# 24-SMD-adapter.net
KiCad netlist of a schematic drawn in EAGLE
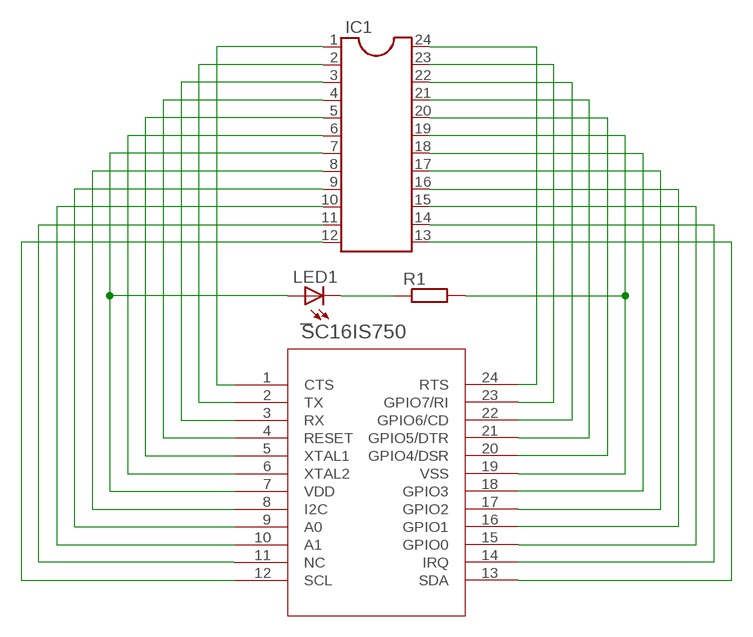
[diagram p0: schematic, sheet 1]

(export (version "E")
  (design (tool "Eeschema 10.0.6"))
  (components
    (comp (ref "IC1")
      (value "DIL24-6")
      (footprint "eagle-import:DIL24-6")
      (libsource (lib "eagle-import") (part "DIL24-6"))
    )
    (comp (ref "LED1")
      (value "LEDSML1206")
      (footprint "eagle-import:SML1206")
      (libsource (lib "eagle-import") (part "LEDSML1206"))
    )
    (comp (ref "R1")
      (value "R-EU_R0402")
      (footprint "eagle-import:R0402")
      (libsource (lib "eagle-import") (part "R-EU_R0402"))
    )
    (comp (ref "_")
      (value "SC16IS750")
      (footprint "eagle-import:SOT361_1_M")
      (libsource (lib "eagle-import") (part "SC16IS750"))
    )
  )
  (nets
    (net (code "1") (name "Net-(LED1-PadC)") (class "Default")
      (node (ref "LED1") (pin "C") (pinfunction "C_C") (pintype "passive"))
      (node (ref "R1") (pin "1") (pinfunction "1_1") (pintype "passive"))
    )
    (net (code "2") (name "Net-(_-A0)") (class "Default")
      (node (ref "IC1") (pin "9") (pinfunction "9_9") (pintype "passive"))
      (node (ref "_") (pin "9") (pinfunction "A0_9") (pintype "passive"))
    )
    (net (code "3") (name "Net-(_-A1)") (class "Default")
      (node (ref "IC1") (pin "10") (pinfunction "10_10") (pintype "passive"))
      (node (ref "_") (pin "10") (pinfunction "A1_10") (pintype "passive"))
    )
    (net (code "4") (name "Net-(_-CTS)") (class "Default")
      (node (ref "IC1") (pin "1") (pinfunction "1_1") (pintype "passive"))
      (node (ref "_") (pin "1") (pinfunction "CTS_1") (pintype "passive"))
    )
    (net (code "5") (name "Net-(_-GPIO0)") (class "Default")
      (node (ref "IC1") (pin "15") (pinfunction "15_15") (pintype "passive"))
      (node (ref "_") (pin "15") (pinfunction "GPIO0_15") (pintype "passive"))
    )
    (net (code "6") (name "Net-(_-GPIO1)") (class "Default")
      (node (ref "IC1") (pin "16") (pinfunction "16_16") (pintype "passive"))
      (node (ref "_") (pin "16") (pinfunction "GPIO1_16") (pintype "passive"))
    )
    (net (code "7") (name "Net-(_-GPIO2)") (class "Default")
      (node (ref "IC1") (pin "17") (pinfunction "17_17") (pintype "passive"))
      (node (ref "_") (pin "17") (pinfunction "GPIO2_17") (pintype "passive"))
    )
    (net (code "8") (name "Net-(_-GPIO3)") (class "Default")
      (node (ref "IC1") (pin "18") (pinfunction "18_18") (pintype "passive"))
      (node (ref "_") (pin "18") (pinfunction "GPIO3_18") (pintype "passive"))
    )
    (net (code "9") (name "Net-(_-GPIO4{slash}DSR)") (class "Default")
      (node (ref "IC1") (pin "20") (pinfunction "20_20") (pintype "passive"))
      (node (ref "_") (pin "20") (pinfunction "GPIO4/DSR_20") (pintype "passive"))
    )
    (net (code "10") (name "Net-(_-GPIO5{slash}DTR)") (class "Default")
      (node (ref "IC1") (pin "21") (pinfunction "21_21") (pintype "passive"))
      (node (ref "_") (pin "21") (pinfunction "GPIO5/DTR_21") (pintype "passive"))
    )
    (net (code "11") (name "Net-(_-GPIO6{slash}CD)") (class "Default")
      (node (ref "IC1") (pin "22") (pinfunction "22_22") (pintype "passive"))
      (node (ref "_") (pin "22") (pinfunction "GPIO6/CD_22") (pintype "passive"))
    )
    (net (code "12") (name "Net-(_-GPIO7{slash}RI)") (class "Default")
      (node (ref "IC1") (pin "23") (pinfunction "23_23") (pintype "passive"))
      (node (ref "_") (pin "23") (pinfunction "GPIO7/RI_23") (pintype "passive"))
    )
    (net (code "13") (name "Net-(_-I2C)") (class "Default")
      (node (ref "IC1") (pin "8") (pinfunction "8_8") (pintype "passive"))
      (node (ref "_") (pin "8") (pinfunction "I2C_8") (pintype "passive"))
    )
    (net (code "14") (name "Net-(_-IRQ)") (class "Default")
      (node (ref "IC1") (pin "14") (pinfunction "14_14") (pintype "passive"))
      (node (ref "_") (pin "14") (pinfunction "IRQ_14") (pintype "passive"))
    )
    (net (code "15") (name "Net-(_-NC)") (class "Default")
      (node (ref "IC1") (pin "11") (pinfunction "11_11") (pintype "passive"))
      (node (ref "_") (pin "11") (pinfunction "NC_11") (pintype "passive"))
    )
    (net (code "16") (name "Net-(_-RESET)") (class "Default")
      (node (ref "IC1") (pin "4") (pinfunction "4_4") (pintype "passive"))
      (node (ref "_") (pin "4") (pinfunction "RESET_4") (pintype "passive"))
    )
    (net (code "17") (name "Net-(_-RTS)") (class "Default")
      (node (ref "IC1") (pin "24") (pinfunction "24_24") (pintype "passive"))
      (node (ref "_") (pin "24") (pinfunction "RTS_24") (pintype "passive"))
    )
    (net (code "18") (name "Net-(_-RX)") (class "Default")
      (node (ref "IC1") (pin "3") (pinfunction "3_3") (pintype "passive"))
      (node (ref "_") (pin "3") (pinfunction "RX_3") (pintype "passive"))
    )
    (net (code "19") (name "Net-(_-SCL)") (class "Default")
      (node (ref "IC1") (pin "12") (pinfunction "12_12") (pintype "passive"))
      (node (ref "_") (pin "12") (pinfunction "SCL_12") (pintype "passive"))
    )
    (net (code "20") (name "Net-(_-SDA)") (class "Default")
      (node (ref "IC1") (pin "13") (pinfunction "13_13") (pintype "passive"))
      (node (ref "_") (pin "13") (pinfunction "SDA_13") (pintype "passive"))
    )
    (net (code "21") (name "Net-(_-TX)") (class "Default")
      (node (ref "IC1") (pin "2") (pinfunction "2_2") (pintype "passive"))
      (node (ref "_") (pin "2") (pinfunction "TX_2") (pintype "passive"))
    )
    (net (code "22") (name "Net-(_-VDD)") (class "Default")
      (node (ref "IC1") (pin "7") (pinfunction "7_7") (pintype "passive"))
      (node (ref "LED1") (pin "A") (pinfunction "A_A") (pintype "passive"))
      (node (ref "_") (pin "7") (pinfunction "VDD_7") (pintype "passive"))
    )
    (net (code "23") (name "Net-(_-VSS)") (class "Default")
      (node (ref "IC1") (pin "19") (pinfunction "19_19") (pintype "passive"))
      (node (ref "R1") (pin "2") (pinfunction "2_2") (pintype "passive"))
      (node (ref "_") (pin "19") (pinfunction "VSS_19") (pintype "passive"))
    )
    (net (code "24") (name "Net-(_-XTAL1)") (class "Default")
      (node (ref "IC1") (pin "5") (pinfunction "5_5") (pintype "passive"))
      (node (ref "_") (pin "5") (pinfunction "XTAL1_5") (pintype "passive"))
    )
    (net (code "25") (name "Net-(_-XTAL2)") (class "Default")
      (node (ref "IC1") (pin "6") (pinfunction "6_6") (pintype "passive"))
      (node (ref "_") (pin "6") (pinfunction "XTAL2_6") (pintype "passive"))
    )
  )
)
